# CapePowerSupplyModule.net
KiCad netlist of a schematic drawn in EAGLE
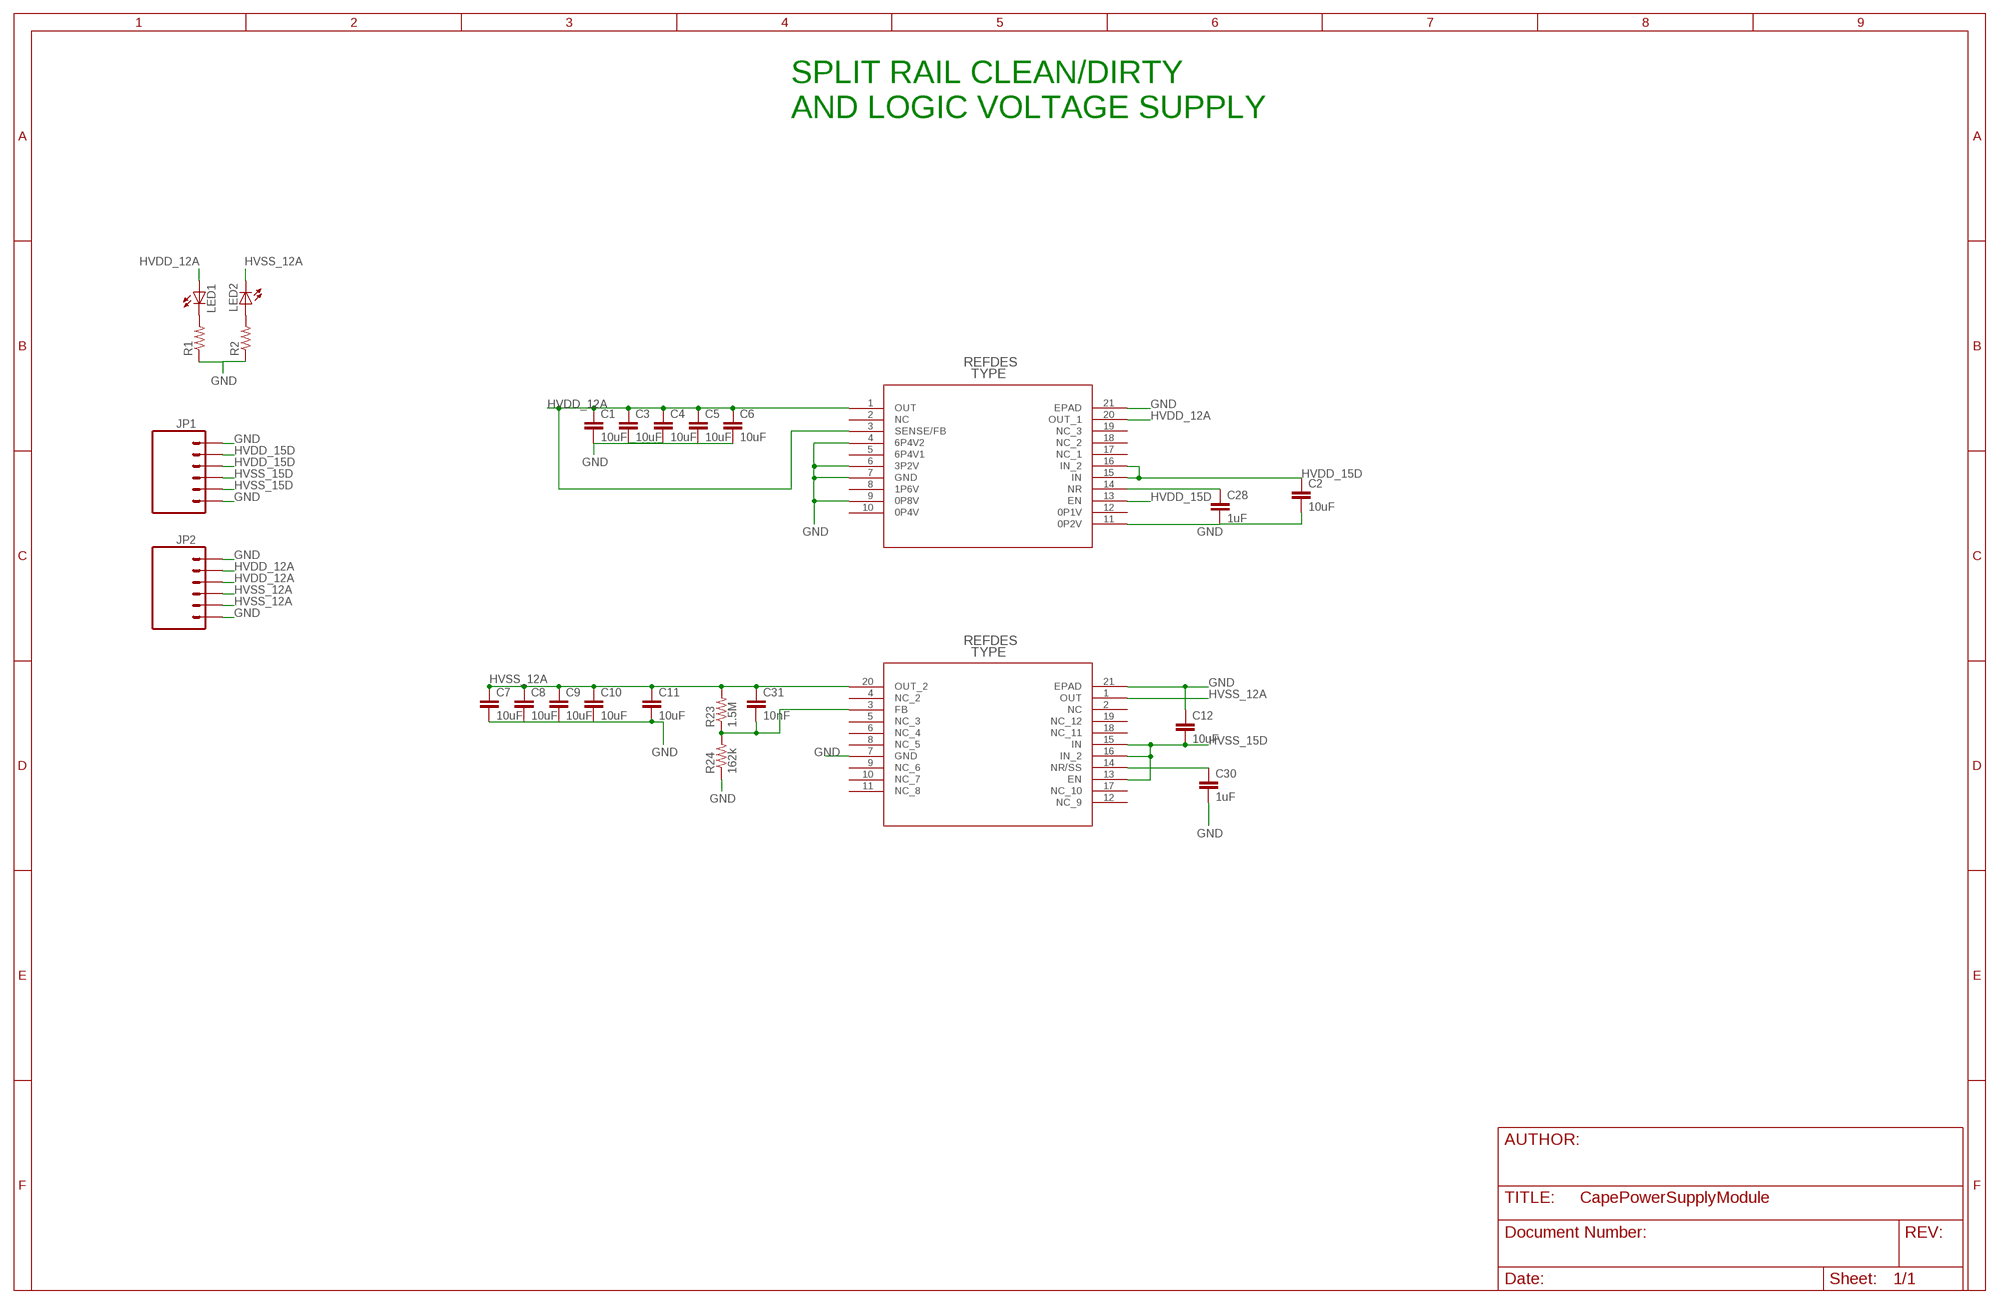
[diagram p0: schematic, sheet 1]

(export (version "E")
  (design (tool "Eeschema 10.0.6"))
  (components
    (comp (ref "C1")
      (value "10uF")
      (footprint "eagle-import:1206")
      (libsource (lib "eagle-import") (part "CAP1206"))
    )
    (comp (ref "C2")
      (value "10uF")
      (footprint "eagle-import:1206")
      (libsource (lib "eagle-import") (part "CAP1206"))
    )
    (comp (ref "C3")
      (value "10uF")
      (footprint "eagle-import:1206")
      (libsource (lib "eagle-import") (part "CAP1206"))
    )
    (comp (ref "C4")
      (value "10uF")
      (footprint "eagle-import:1206")
      (libsource (lib "eagle-import") (part "CAP1206"))
    )
    (comp (ref "C5")
      (value "10uF")
      (footprint "eagle-import:1206")
      (libsource (lib "eagle-import") (part "CAP1206"))
    )
    (comp (ref "C6")
      (value "10uF")
      (footprint "eagle-import:1206")
      (libsource (lib "eagle-import") (part "CAP1206"))
    )
    (comp (ref "C7")
      (value "10uF")
      (footprint "eagle-import:1206")
      (libsource (lib "eagle-import") (part "CAP1206"))
    )
    (comp (ref "C8")
      (value "10uF")
      (footprint "eagle-import:1206")
      (libsource (lib "eagle-import") (part "CAP1206"))
    )
    (comp (ref "C9")
      (value "10uF")
      (footprint "eagle-import:1206")
      (libsource (lib "eagle-import") (part "CAP1206"))
    )
    (comp (ref "C10")
      (value "10uF")
      (footprint "eagle-import:1206")
      (libsource (lib "eagle-import") (part "CAP1206"))
    )
    (comp (ref "C11")
      (value "10uF")
      (footprint "eagle-import:1206")
      (libsource (lib "eagle-import") (part "CAP1206"))
    )
    (comp (ref "C12")
      (value "10uF")
      (footprint "eagle-import:1206")
      (libsource (lib "eagle-import") (part "CAP1206"))
    )
    (comp (ref "C28")
      (value "1uF")
      (footprint "eagle-import:0805")
      (libsource (lib "eagle-import") (part "CAP0805"))
    )
    (comp (ref "C30")
      (value "1uF")
      (footprint "eagle-import:0805")
      (libsource (lib "eagle-import") (part "CAP0805"))
    )
    (comp (ref "C31")
      (value "10nF")
      (footprint "eagle-import:0805")
      (libsource (lib "eagle-import") (part "CAP0805"))
    )
    (comp (ref "JP1")
      (value "M06LOCK")
      (footprint "eagle-import:1X06_LOCK")
      (libsource (lib "eagle-import") (part "M06LOCK"))
    )
    (comp (ref "JP2")
      (value "M06LOCK")
      (footprint "eagle-import:1X06_LOCK")
      (libsource (lib "eagle-import") (part "M06LOCK"))
    )
    (comp (ref "LED1")
      (value "LED1206")
      (footprint "eagle-import:LED-1206")
      (libsource (lib "eagle-import") (part "LED1206"))
    )
    (comp (ref "LED2")
      (value "LED1206")
      (footprint "eagle-import:LED-1206")
      (libsource (lib "eagle-import") (part "LED1206"))
    )
    (comp (ref "R1")
      (value "RESISTOR0805-RES")
      (footprint "eagle-import:0805")
      (libsource (lib "eagle-import") (part "SensorCape_RESISTOR0805-RES"))
    )
    (comp (ref "R2")
      (value "RESISTOR0805-RES")
      (footprint "eagle-import:0805")
      (libsource (lib "eagle-import") (part "SensorCape_RESISTOR0805-RES"))
    )
    (comp (ref "R23")
      (value "1.5M")
      (footprint "eagle-import:0805")
      (libsource (lib "eagle-import") (part "RESISTOR0805-RES"))
    )
    (comp (ref "R24")
      (value "162k")
      (footprint "eagle-import:0805")
      (libsource (lib "eagle-import") (part "RESISTOR0805-RES"))
    )
    (comp (ref "U$3")
      (value "TPS7A4700_RGW_20")
      (footprint "eagle-import:RGW20_3P15X3P15")
      (libsource (lib "eagle-import") (part "TPS7A4700_RGW_20"))
    )
    (comp (ref "U6")
      (value "TPS7A3301_RGW_20")
      (footprint "eagle-import:RGW20_3P15X3P15")
      (libsource (lib "eagle-import") (part "TPS7A3301_RGW_20"))
    )
  )
  (nets
    (net (code "1") (name "/GND") (class "Default")
      (node (ref "C1") (pin "2") (pinfunction "2_2") (pintype "passive"))
      (node (ref "C10") (pin "2") (pinfunction "2_2") (pintype "passive"))
      (node (ref "C11") (pin "2") (pinfunction "2_2") (pintype "passive"))
      (node (ref "C12") (pin "1") (pinfunction "1_1") (pintype "passive"))
      (node (ref "C2") (pin "2") (pinfunction "2_2") (pintype "passive"))
      (node (ref "C28") (pin "2") (pinfunction "2_2") (pintype "passive"))
      (node (ref "C3") (pin "2") (pinfunction "2_2") (pintype "passive"))
      (node (ref "C30") (pin "2") (pinfunction "2_2") (pintype "passive"))
      (node (ref "C4") (pin "2") (pinfunction "2_2") (pintype "passive"))
      (node (ref "C5") (pin "2") (pinfunction "2_2") (pintype "passive"))
      (node (ref "C6") (pin "2") (pinfunction "2_2") (pintype "passive"))
      (node (ref "C7") (pin "2") (pinfunction "2_2") (pintype "passive"))
      (node (ref "C8") (pin "2") (pinfunction "2_2") (pintype "passive"))
      (node (ref "C9") (pin "2") (pinfunction "2_2") (pintype "passive"))
      (node (ref "JP1") (pin "1") (pinfunction "1_1") (pintype "passive"))
      (node (ref "JP1") (pin "6") (pinfunction "6_6") (pintype "passive"))
      (node (ref "JP2") (pin "1") (pinfunction "1_1") (pintype "passive"))
      (node (ref "JP2") (pin "6") (pinfunction "6_6") (pintype "passive"))
      (node (ref "R1") (pin "1") (pinfunction "1_1") (pintype "passive"))
      (node (ref "R2") (pin "1") (pinfunction "1_1") (pintype "passive"))
      (node (ref "R24") (pin "1") (pinfunction "1_1") (pintype "passive"))
      (node (ref "U$3") (pin "11") (pinfunction "0P2V_11") (pintype "passive"))
      (node (ref "U$3") (pin "21") (pinfunction "EPAD_21") (pintype "passive"))
      (node (ref "U$3") (pin "4") (pinfunction "6P4V2_4") (pintype "passive"))
      (node (ref "U$3") (pin "6") (pinfunction "3P2V_6") (pintype "passive"))
      (node (ref "U$3") (pin "7") (pinfunction "GND_7") (pintype "passive"))
      (node (ref "U$3") (pin "9") (pinfunction "0P8V_9") (pintype "passive"))
      (node (ref "U6") (pin "21") (pinfunction "EPAD_21") (pintype "passive"))
      (node (ref "U6") (pin "7") (pinfunction "GND_7") (pintype "passive"))
    )
    (net (code "2") (name "/HVDD_12A") (class "Default")
      (node (ref "C1") (pin "1") (pinfunction "1_1") (pintype "passive"))
      (node (ref "C3") (pin "1") (pinfunction "1_1") (pintype "passive"))
      (node (ref "C4") (pin "1") (pinfunction "1_1") (pintype "passive"))
      (node (ref "C5") (pin "1") (pinfunction "1_1") (pintype "passive"))
      (node (ref "C6") (pin "1") (pinfunction "1_1") (pintype "passive"))
      (node (ref "JP2") (pin "2") (pinfunction "2_2") (pintype "passive"))
      (node (ref "JP2") (pin "3") (pinfunction "3_3") (pintype "passive"))
      (node (ref "LED1") (pin "A") (pinfunction "A_A") (pintype "passive"))
      (node (ref "U$3") (pin "1") (pinfunction "OUT_1") (pintype "passive"))
      (node (ref "U$3") (pin "20") (pinfunction "OUT_1_20") (pintype "passive"))
      (node (ref "U$3") (pin "3") (pinfunction "SENSE/FB_3") (pintype "passive"))
    )
    (net (code "3") (name "/HVDD_15D") (class "Default")
      (node (ref "C2") (pin "1") (pinfunction "1_1") (pintype "passive"))
      (node (ref "JP1") (pin "2") (pinfunction "2_2") (pintype "passive"))
      (node (ref "JP1") (pin "3") (pinfunction "3_3") (pintype "passive"))
      (node (ref "U$3") (pin "13") (pinfunction "EN_13") (pintype "passive"))
      (node (ref "U$3") (pin "15") (pinfunction "IN_15") (pintype "passive"))
      (node (ref "U$3") (pin "16") (pinfunction "IN_2_16") (pintype "passive"))
    )
    (net (code "4") (name "/HVSS_12A") (class "Default")
      (node (ref "C10") (pin "1") (pinfunction "1_1") (pintype "passive"))
      (node (ref "C11") (pin "1") (pinfunction "1_1") (pintype "passive"))
      (node (ref "C31") (pin "1") (pinfunction "1_1") (pintype "passive"))
      (node (ref "C7") (pin "1") (pinfunction "1_1") (pintype "passive"))
      (node (ref "C8") (pin "1") (pinfunction "1_1") (pintype "passive"))
      (node (ref "C9") (pin "1") (pinfunction "1_1") (pintype "passive"))
      (node (ref "JP2") (pin "4") (pinfunction "4_4") (pintype "passive"))
      (node (ref "JP2") (pin "5") (pinfunction "5_5") (pintype "passive"))
      (node (ref "LED2") (pin "C") (pinfunction "C_C") (pintype "passive"))
      (node (ref "R23") (pin "2") (pinfunction "2_2") (pintype "passive"))
      (node (ref "U6") (pin "1") (pinfunction "OUT_1") (pintype "passive"))
      (node (ref "U6") (pin "20") (pinfunction "OUT_2_20") (pintype "passive"))
    )
    (net (code "5") (name "/HVSS_15D") (class "Default")
      (node (ref "C12") (pin "2") (pinfunction "2_2") (pintype "passive"))
      (node (ref "JP1") (pin "4") (pinfunction "4_4") (pintype "passive"))
      (node (ref "JP1") (pin "5") (pinfunction "5_5") (pintype "passive"))
      (node (ref "U6") (pin "13") (pinfunction "EN_13") (pintype "passive"))
      (node (ref "U6") (pin "15") (pinfunction "IN_15") (pintype "passive"))
      (node (ref "U6") (pin "16") (pinfunction "IN_2_16") (pintype "passive"))
    )
    (net (code "6") (name "Net-(LED1-PadC)") (class "Default")
      (node (ref "LED1") (pin "C") (pinfunction "C_C") (pintype "passive"))
      (node (ref "R1") (pin "2") (pinfunction "2_2") (pintype "passive"))
    )
    (net (code "7") (name "Net-(LED2-PadA)") (class "Default")
      (node (ref "LED2") (pin "A") (pinfunction "A_A") (pintype "passive"))
      (node (ref "R2") (pin "2") (pinfunction "2_2") (pintype "passive"))
    )
    (net (code "8") (name "Net-(U$3-NR)") (class "Default")
      (node (ref "C28") (pin "1") (pinfunction "1_1") (pintype "passive"))
      (node (ref "U$3") (pin "14") (pinfunction "NR_14") (pintype "passive"))
    )
    (net (code "9") (name "Net-(U6-FB)") (class "Default")
      (node (ref "C31") (pin "2") (pinfunction "2_2") (pintype "passive"))
      (node (ref "R23") (pin "1") (pinfunction "1_1") (pintype "passive"))
      (node (ref "R24") (pin "2") (pinfunction "2_2") (pintype "passive"))
      (node (ref "U6") (pin "3") (pinfunction "FB_3") (pintype "passive"))
    )
    (net (code "10") (name "Net-(U6-NR{slash}SS)") (class "Default")
      (node (ref "C30") (pin "1") (pinfunction "1_1") (pintype "passive"))
      (node (ref "U6") (pin "14") (pinfunction "NR/SS_14") (pintype "passive"))
    )
    (net (code "11") (name "unconnected-(U$3-0P1V-Pad12)") (class "Default")
      (node (ref "U$3") (pin "12") (pinfunction "0P1V_12") (pintype "passive"))
    )
    (net (code "12") (name "unconnected-(U$3-0P4V-Pad10)") (class "Default")
      (node (ref "U$3") (pin "10") (pinfunction "0P4V_10") (pintype "passive"))
    )
    (net (code "13") (name "unconnected-(U$3-1P6V-Pad8)") (class "Default")
      (node (ref "U$3") (pin "8") (pinfunction "1P6V_8") (pintype "passive"))
    )
    (net (code "14") (name "unconnected-(U$3-6P4V1-Pad5)") (class "Default")
      (node (ref "U$3") (pin "5") (pinfunction "6P4V1_5") (pintype "passive"))
    )
    (net (code "15") (name "unconnected-(U$3-NC-Pad2)") (class "Default")
      (node (ref "U$3") (pin "2") (pinfunction "NC_2") (pintype "passive"))
    )
    (net (code "16") (name "unconnected-(U$3-NC_1-Pad17)") (class "Default")
      (node (ref "U$3") (pin "17") (pinfunction "NC_1_17") (pintype "passive"))
    )
    (net (code "17") (name "unconnected-(U$3-NC_2-Pad18)") (class "Default")
      (node (ref "U$3") (pin "18") (pinfunction "NC_2_18") (pintype "passive"))
    )
    (net (code "18") (name "unconnected-(U$3-NC_3-Pad19)") (class "Default")
      (node (ref "U$3") (pin "19") (pinfunction "NC_3_19") (pintype "passive"))
    )
    (net (code "19") (name "unconnected-(U6-NC-Pad2)") (class "Default")
      (node (ref "U6") (pin "2") (pinfunction "NC_2") (pintype "passive"))
    )
    (net (code "20") (name "unconnected-(U6-NC_2-Pad4)") (class "Default")
      (node (ref "U6") (pin "4") (pinfunction "NC_2_4") (pintype "passive"))
    )
    (net (code "21") (name "unconnected-(U6-NC_3-Pad5)") (class "Default")
      (node (ref "U6") (pin "5") (pinfunction "NC_3_5") (pintype "passive"))
    )
    (net (code "22") (name "unconnected-(U6-NC_4-Pad6)") (class "Default")
      (node (ref "U6") (pin "6") (pinfunction "NC_4_6") (pintype "passive"))
    )
    (net (code "23") (name "unconnected-(U6-NC_5-Pad8)") (class "Default")
      (node (ref "U6") (pin "8") (pinfunction "NC_5_8") (pintype "passive"))
    )
    (net (code "24") (name "unconnected-(U6-NC_6-Pad9)") (class "Default")
      (node (ref "U6") (pin "9") (pinfunction "NC_6_9") (pintype "passive"))
    )
    (net (code "25") (name "unconnected-(U6-NC_7-Pad10)") (class "Default")
      (node (ref "U6") (pin "10") (pinfunction "NC_7_10") (pintype "passive"))
    )
    (net (code "26") (name "unconnected-(U6-NC_8-Pad11)") (class "Default")
      (node (ref "U6") (pin "11") (pinfunction "NC_8_11") (pintype "passive"))
    )
    (net (code "27") (name "unconnected-(U6-NC_9-Pad12)") (class "Default")
      (node (ref "U6") (pin "12") (pinfunction "NC_9_12") (pintype "passive"))
    )
    (net (code "28") (name "unconnected-(U6-NC_10-Pad17)") (class "Default")
      (node (ref "U6") (pin "17") (pinfunction "NC_10_17") (pintype "passive"))
    )
    (net (code "29") (name "unconnected-(U6-NC_11-Pad18)") (class "Default")
      (node (ref "U6") (pin "18") (pinfunction "NC_11_18") (pintype "passive"))
    )
    (net (code "30") (name "unconnected-(U6-NC_12-Pad19)") (class "Default")
      (node (ref "U6") (pin "19") (pinfunction "NC_12_19") (pintype "passive"))
    )
  )
)
